# MCU.net
KiCad netlist of a schematic drawn in Altium Designer
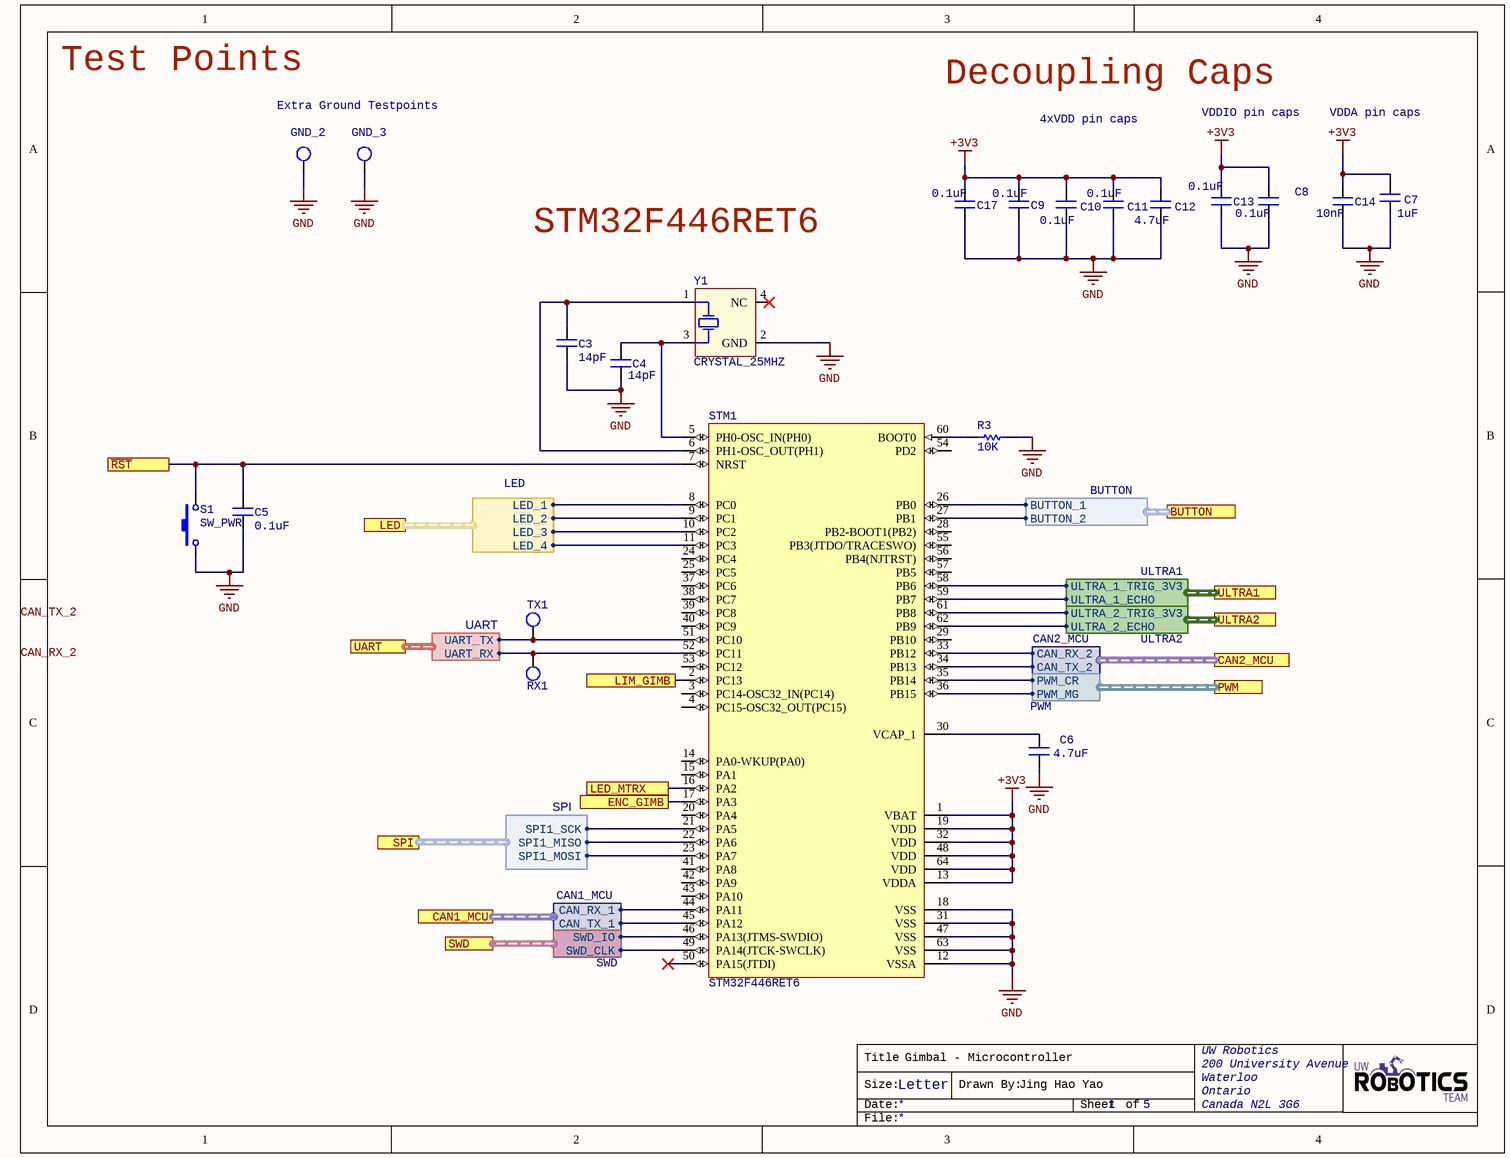
[diagram p0: MCU.SchDoc]

(export (version "E")
  (design (tool "Eeschema 10.0.6"))
  (components
    (comp (ref "C3")
      (value "14pF")
      (footprint "CAPC0603(1608)55_N")
      (description "Cap Ceramic 14pF 50V C0G 5% SMD 0603 125C Cardboard T/R")
      (fields (field (name "TOLERANCE") "5%") (field (name "Comment") "CL10C140JB8NNNC"))
      (libsource (lib "UWRT_Schematic_Library_2020") (part "CL10C140JB8NNNC"))
    )
    (comp (ref "C4")
      (value "14pF")
      (footprint "CAPC0603(1608)55_N")
      (description "Cap Ceramic 14pF 50V C0G 5% SMD 0603 125C Cardboard T/R")
      (fields (field (name "TOLERANCE") "5%") (field (name "Comment") "CL10C140JB8NNNC"))
      (libsource (lib "UWRT_Schematic_Library_2020") (part "CL10C140JB8NNNC"))
    )
    (comp (ref "C5")
      (value "0.1uF")
      (footprint "CAPC0603(1608)55_N")
      (description "CAP CER 0.1UF 16V X7R 0603")
      (fields (field (name "MANUFACTURER") "Yageo") (field (name "MPN") "CC0603KRX7R7BB104"))
      (libsource (lib "UWRT_Schematic_Library_2020") (part "CAP_0.1uF_16V_0603"))
    )
    (comp (ref "C6")
      (value "4.7uF")
      (footprint "CAPC0603(1608)55_N")
      (description "CAP CER 4.7UF 6.3V X5R 0603")
      (fields (field (name "MANUFACTURER") "Yageo") (field (name "MPN") "CC0603KRX5R5BB475"))
      (libsource (lib "UWRT_Schematic_Library_2020") (part "CAP_4.7uF_0603"))
    )
    (comp (ref "C7")
      (value "1uF")
      (footprint "CAPC0603(1608)55_N")
      (description "CAP CER 1UF 16V Y5V 0603")
      (fields (field (name "MANUFACTURER") "Yageo") (field (name "MPN") "CC0603ZRY5V7BB105"))
      (libsource (lib "UWRT_Schematic_Library_2020") (part "CAP_1uF_16V_0603"))
    )
    (comp (ref "C8")
      (value "0.1uF")
      (footprint "CAPC0603(1608)55_N")
      (description "CAP CER 0.1UF 16V X7R 0603")
      (fields (field (name "MANUFACTURER") "Yageo") (field (name "MPN") "CC0603KRX7R7BB104"))
      (libsource (lib "UWRT_Schematic_Library_2020") (part "CAP_0.1uF_16V_0603"))
    )
    (comp (ref "C9")
      (value "0.1uF")
      (footprint "CAPC0603(1608)55_N")
      (description "CAP CER 0.1UF 16V X7R 0603")
      (fields (field (name "MANUFACTURER") "Yageo") (field (name "MPN") "CC0603KRX7R7BB104"))
      (libsource (lib "UWRT_Schematic_Library_2020") (part "CAP_0.1uF_16V_0603"))
    )
    (comp (ref "C10")
      (value "0.1uF")
      (footprint "CAPC0603(1608)55_N")
      (description "CAP CER 0.1UF 16V X7R 0603")
      (fields (field (name "MANUFACTURER") "Yageo") (field (name "MPN") "CC0603KRX7R7BB104"))
      (libsource (lib "UWRT_Schematic_Library_2020") (part "CAP_0.1uF_16V_0603"))
    )
    (comp (ref "C11")
      (value "0.1uF")
      (footprint "CAPC0603(1608)55_N")
      (description "CAP CER 0.1UF 16V X7R 0603")
      (fields (field (name "MANUFACTURER") "Yageo") (field (name "MPN") "CC0603KRX7R7BB104"))
      (libsource (lib "UWRT_Schematic_Library_2020") (part "CAP_0.1uF_16V_0603"))
    )
    (comp (ref "C12")
      (value "4.7uF")
      (footprint "CAPC0603(1608)55_N")
      (description "CAP CER 4.7UF 6.3V X5R 0603")
      (fields (field (name "MANUFACTURER") "Yageo") (field (name "MPN") "CC0603KRX5R5BB475"))
      (libsource (lib "UWRT_Schematic_Library_2020") (part "CAP_4.7uF_0603"))
    )
    (comp (ref "C13")
      (value "0.1uF")
      (footprint "CAPC0603(1608)55_N")
      (description "CAP CER 0.1UF 16V X7R 0603")
      (fields (field (name "MANUFACTURER") "Yageo") (field (name "MPN") "CC0603KRX7R7BB104"))
      (libsource (lib "UWRT_Schematic_Library_2020") (part "CAP_0.1uF_16V_0603"))
    )
    (comp (ref "C14")
      (value "10nF")
      (footprint "CAPC0603(1608)55_N")
      (description "CAP CER 10000PF 16V X7R 0603")
      (fields (field (name "MANUFACTURER") "Yageo") (field (name "MPN") "CC0603KRX7R7BB103"))
      (libsource (lib "UWRT_Schematic_Library_2020") (part "CAP_10nF_0603"))
    )
    (comp (ref "C17")
      (value "0.1uF")
      (footprint "CAPC0603(1608)55_N")
      (description "CAP CER 0.1UF 16V X7R 0603")
      (fields (field (name "MANUFACTURER") "Yageo") (field (name "MPN") "CC0603KRX7R7BB104"))
      (libsource (lib "UWRT_Schematic_Library_2020") (part "CAP_0.1uF_16V_0603"))
    )
    (comp (ref "GND_2")
      (value "TESTPOINT_LOOP")
      (footprint "TESTPOINT_LOOP")
      (description "Loop testpoint through-hole pad")
      (fields (field (name "MANUFACTURER") "Keystone Electronics"))
      (libsource (lib "UWRT_Schematic_Library_2020") (part "TESTPOINT_LOOP"))
    )
    (comp (ref "GND_3")
      (value "TESTPOINT_LOOP")
      (footprint "TESTPOINT_LOOP")
      (description "Loop testpoint through-hole pad")
      (fields (field (name "MANUFACTURER") "Keystone Electronics"))
      (libsource (lib "UWRT_Schematic_Library_2020") (part "TESTPOINT_LOOP"))
    )
    (comp (ref "R3")
      (value "10K")
      (footprint "RESC0603(1608)_N")
      (description "RES SMD 10K OHM 5% 1/10W 0603")
      (fields (field (name "MANUFACTURER") "Yageo") (field (name "MPN") "RC0603JR-0710KL"))
      (libsource (lib "UWRT_Schematic_Library_2020") (part "RES_10K_0603"))
    )
    (comp (ref "RX1")
      (value "TESTPOINT_LOOP")
      (footprint "TESTPOINT_LOOP")
      (description "Loop testpoint through-hole pad")
      (fields (field (name "MANUFACTURER") "Keystone Electronics"))
      (libsource (lib "UWRT_Schematic_Library_2020") (part "TESTPOINT_LOOP"))
    )
    (comp (ref "S1")
      (value "SW_PWR")
      (footprint "PTS830GM140")
      (description "Power Switch (Red)")
      (fields (field (name "MPN") "PTS830GM140 SMTR LFS") (field (name "MANUFACTURER") "C&K"))
      (libsource (lib "UWRT_Schematic_Library_2020") (part "SW_PWR"))
    )
    (comp (ref "STM1")
      (value "STM32F446RET6")
      (footprint "STM-LQFP64_L")
      (libsource (lib "UWRT_Schematic_Library_2020") (part "MCU_STM32F446RET6"))
    )
    (comp (ref "TX1")
      (value "TESTPOINT_LOOP")
      (footprint "TESTPOINT_LOOP")
      (description "Loop testpoint through-hole pad")
      (fields (field (name "MANUFACTURER") "Keystone Electronics"))
      (libsource (lib "UWRT_Schematic_Library_2020") (part "TESTPOINT_LOOP"))
    )
    (comp (ref "Y1")
      (value "CRYSTAL_25MHZ")
      (footprint "AVX-CX2520DB32000D0GEJZ1-4_V")
      (description "CRYSTAL 25.0000MHZ 12PF SMD")
      (libsource (lib "UWRT_Schematic_Library_2020") (part "CRYSTAL_25MHZ"))
    )
  )
  (nets
    (net (code "11") (name "+3V3") (class "Default")
      (node (ref "C10") (pin "2") (pinfunction "2_2") (pintype "passive"))
      (node (ref "C11") (pin "2") (pinfunction "2_2") (pintype "passive"))
      (node (ref "C12") (pin "2") (pinfunction "2_2") (pintype "passive"))
      (node (ref "C13") (pin "2") (pinfunction "2_2") (pintype "passive"))
      (node (ref "C14") (pin "2") (pinfunction "2_2") (pintype "passive"))
      (node (ref "C17") (pin "2") (pinfunction "2_2") (pintype "passive"))
      (node (ref "C7") (pin "2") (pinfunction "2_2") (pintype "passive"))
      (node (ref "C8") (pin "2") (pinfunction "2_2") (pintype "passive"))
      (node (ref "C9") (pin "2") (pinfunction "2_2") (pintype "passive"))
      (node (ref "STM1") (pin "1") (pinfunction "VBAT_1") (pintype "power_in"))
      (node (ref "STM1") (pin "13") (pinfunction "VDDA_13") (pintype "power_in"))
      (node (ref "STM1") (pin "19") (pinfunction "VDD_19") (pintype "power_in"))
      (node (ref "STM1") (pin "32") (pinfunction "VDD_32") (pintype "power_in"))
      (node (ref "STM1") (pin "48") (pinfunction "VDD_48") (pintype "power_in"))
      (node (ref "STM1") (pin "64") (pinfunction "VDD_64") (pintype "power_in"))
    )
    (net (code "12") (name "/BUTTON_1") (class "Default")
      (node (ref "STM1") (pin "26") (pinfunction "PB0_26") (pintype "bidirectional"))
    )
    (net (code "13") (name "/BUTTON_2") (class "Default")
      (node (ref "STM1") (pin "27") (pinfunction "PB1_27") (pintype "bidirectional"))
    )
    (net (code "14") (name "/CAN_RX_1") (class "Default")
      (node (ref "STM1") (pin "44") (pinfunction "PA11_44") (pintype "bidirectional"))
    )
    (net (code "16") (name "/CAN_TX_1") (class "Default")
      (node (ref "STM1") (pin "45") (pinfunction "PA12_45") (pintype "bidirectional"))
    )
    (net (code "18") (name "/ENC_GIMB") (class "Default")
      (node (ref "STM1") (pin "17") (pinfunction "PA3_17") (pintype "bidirectional"))
    )
    (net (code "19") (name "/LED_1") (class "Default")
      (node (ref "STM1") (pin "8") (pinfunction "PC0_8") (pintype "bidirectional"))
    )
    (net (code "20") (name "/LED_2") (class "Default")
      (node (ref "STM1") (pin "9") (pinfunction "PC1_9") (pintype "bidirectional"))
    )
    (net (code "21") (name "/LED_3") (class "Default")
      (node (ref "STM1") (pin "10") (pinfunction "PC2_10") (pintype "bidirectional"))
    )
    (net (code "22") (name "/LED_4") (class "Default")
      (node (ref "STM1") (pin "11") (pinfunction "PC3_11") (pintype "bidirectional"))
    )
    (net (code "23") (name "/LED_MTRX") (class "Default")
      (node (ref "STM1") (pin "16") (pinfunction "PA2_16") (pintype "bidirectional"))
    )
    (net (code "24") (name "/LIM_GIMB") (class "Default")
      (node (ref "STM1") (pin "2") (pinfunction "PC13_2") (pintype "bidirectional"))
    )
    (net (code "25") (name "/PWM_CR") (class "Default")
      (node (ref "STM1") (pin "35") (pinfunction "PB14_35") (pintype "bidirectional"))
    )
    (net (code "26") (name "/PWM_MG") (class "Default")
      (node (ref "STM1") (pin "36") (pinfunction "PB15_36") (pintype "bidirectional"))
    )
    (net (code "27") (name "/SPI1_MISO") (class "Default")
      (node (ref "STM1") (pin "22") (pinfunction "PA6_22") (pintype "bidirectional"))
    )
    (net (code "28") (name "/SPI1_MOSI") (class "Default")
      (node (ref "STM1") (pin "23") (pinfunction "PA7_23") (pintype "bidirectional"))
    )
    (net (code "29") (name "/SPI1_SCK") (class "Default")
      (node (ref "STM1") (pin "21") (pinfunction "PA5_21") (pintype "bidirectional"))
    )
    (net (code "30") (name "/SWD_CLK") (class "Default")
      (node (ref "STM1") (pin "49") (pinfunction "PA14(JTCK-SWCLK)_49") (pintype "bidirectional"))
    )
    (net (code "31") (name "/SWD_IO") (class "Default")
      (node (ref "STM1") (pin "46") (pinfunction "PA13(JTMS-SWDIO)_46") (pintype "bidirectional"))
    )
    (net (code "32") (name "/UART_RX") (class "Default")
      (node (ref "RX1") (pin "1") (pintype "passive"))
      (node (ref "STM1") (pin "52") (pinfunction "PC11_52") (pintype "bidirectional"))
    )
    (net (code "33") (name "/UART_TX") (class "Default")
      (node (ref "STM1") (pin "51") (pinfunction "PC10_51") (pintype "bidirectional"))
      (node (ref "TX1") (pin "1") (pintype "passive"))
    )
    (net (code "34") (name "/ULTRA_1_ECHO") (class "Default")
      (node (ref "STM1") (pin "59") (pinfunction "PB7_59") (pintype "bidirectional"))
    )
    (net (code "35") (name "/ULTRA_1_TRIG_3V3") (class "Default")
      (node (ref "STM1") (pin "58") (pinfunction "PB6_58") (pintype "bidirectional"))
    )
    (net (code "36") (name "/ULTRA_2_ECHO") (class "Default")
      (node (ref "STM1") (pin "62") (pinfunction "PB9_62") (pintype "bidirectional"))
    )
    (net (code "37") (name "/ULTRA_2_TRIG_3V3") (class "Default")
      (node (ref "STM1") (pin "61") (pinfunction "PB8_61") (pintype "bidirectional"))
    )
    (net (code "48") (name "/~{RST}") (class "Default")
      (node (ref "C5") (pin "2") (pinfunction "2_2") (pintype "passive"))
      (node (ref "S1") (pin "2") (pinfunction "2_2") (pintype "passive"))
      (node (ref "STM1") (pin "7") (pinfunction "NRST_7") (pintype "bidirectional"))
    )
    (net (code "49") (name "GND") (class "Default")
      (node (ref "C10") (pin "1") (pinfunction "1_1") (pintype "passive"))
      (node (ref "C11") (pin "1") (pinfunction "1_1") (pintype "passive"))
      (node (ref "C12") (pin "1") (pinfunction "1_1") (pintype "passive"))
      (node (ref "C13") (pin "1") (pinfunction "1_1") (pintype "passive"))
      (node (ref "C14") (pin "1") (pinfunction "1_1") (pintype "passive"))
      (node (ref "C17") (pin "1") (pinfunction "1_1") (pintype "passive"))
      (node (ref "C3") (pin "1") (pinfunction "1_1") (pintype "passive"))
      (node (ref "C4") (pin "1") (pinfunction "1_1") (pintype "passive"))
      (node (ref "C5") (pin "1") (pinfunction "1_1") (pintype "passive"))
      (node (ref "C6") (pin "1") (pinfunction "1_1") (pintype "passive"))
      (node (ref "C7") (pin "1") (pinfunction "1_1") (pintype "passive"))
      (node (ref "C8") (pin "1") (pinfunction "1_1") (pintype "passive"))
      (node (ref "C9") (pin "1") (pinfunction "1_1") (pintype "passive"))
      (node (ref "GND_2") (pin "1") (pintype "passive"))
      (node (ref "GND_3") (pin "1") (pintype "passive"))
      (node (ref "R3") (pin "2") (pinfunction "2_2") (pintype "passive"))
      (node (ref "S1") (pin "1") (pinfunction "1_1") (pintype "passive"))
      (node (ref "STM1") (pin "12") (pinfunction "VSSA_12") (pintype "power_in"))
      (node (ref "STM1") (pin "18") (pinfunction "VSS_18") (pintype "power_in"))
      (node (ref "STM1") (pin "31") (pinfunction "VSS_31") (pintype "power_in"))
      (node (ref "STM1") (pin "47") (pinfunction "VSS_47") (pintype "power_in"))
      (node (ref "STM1") (pin "63") (pinfunction "VSS_63") (pintype "power_in"))
      (node (ref "Y1") (pin "2") (pinfunction "GND_2") (pintype "power_in"))
    )
    (net (code "50") (name "Net-(STM1-BOOT0)") (class "Default")
      (node (ref "R3") (pin "1") (pinfunction "1_1") (pintype "passive"))
      (node (ref "STM1") (pin "60") (pinfunction "BOOT0_60") (pintype "input"))
    )
    (net (code "51") (name "Net-(STM1-PH0-OSC_IN(PH0))") (class "Default")
      (node (ref "C4") (pin "2") (pinfunction "2_2") (pintype "passive"))
      (node (ref "STM1") (pin "5") (pinfunction "PH0-OSC_IN(PH0)_5") (pintype "bidirectional"))
      (node (ref "Y1") (pin "3") (pinfunction "HOT_3") (pintype "passive"))
    )
    (net (code "52") (name "Net-(STM1-PH1-OSC_OUT(PH1))") (class "Default")
      (node (ref "C3") (pin "2") (pinfunction "2_2") (pintype "passive"))
      (node (ref "STM1") (pin "6") (pinfunction "PH1-OSC_OUT(PH1)_6") (pintype "bidirectional"))
      (node (ref "Y1") (pin "1") (pinfunction "HOT_1") (pintype "passive"))
    )
    (net (code "53") (name "Net-(STM1-VCAP_1)") (class "Default")
      (node (ref "C6") (pin "2") (pinfunction "2_2") (pintype "passive"))
      (node (ref "STM1") (pin "30") (pinfunction "VCAP_1_30") (pintype "passive"))
    )
    (net (code "54") (name "unconnected-(STM1-PA0-WKUP(PA0)-Pad14)") (class "Default")
      (node (ref "STM1") (pin "14") (pinfunction "PA0-WKUP(PA0)_14") (pintype "bidirectional"))
    )
    (net (code "55") (name "unconnected-(STM1-PA1-Pad15)") (class "Default")
      (node (ref "STM1") (pin "15") (pinfunction "PA1_15") (pintype "bidirectional"))
    )
    (net (code "56") (name "unconnected-(STM1-PA4-Pad20)") (class "Default")
      (node (ref "STM1") (pin "20") (pinfunction "PA4_20") (pintype "bidirectional"))
    )
    (net (code "57") (name "unconnected-(STM1-PA8-Pad41)") (class "Default")
      (node (ref "STM1") (pin "41") (pinfunction "PA8_41") (pintype "bidirectional"))
    )
    (net (code "58") (name "unconnected-(STM1-PA9-Pad42)") (class "Default")
      (node (ref "STM1") (pin "42") (pinfunction "PA9_42") (pintype "bidirectional"))
    )
    (net (code "59") (name "unconnected-(STM1-PA10-Pad43)") (class "Default")
      (node (ref "STM1") (pin "43") (pinfunction "PA10_43") (pintype "bidirectional"))
    )
    (net (code "60") (name "unconnected-(STM1-PA15(JTDI)-Pad50)") (class "Default")
      (node (ref "STM1") (pin "50") (pinfunction "PA15(JTDI)_50") (pintype "bidirectional+no_connect"))
    )
    (net (code "61") (name "unconnected-(STM1-PB2-BOOT1(PB2)-Pad28)") (class "Default")
      (node (ref "STM1") (pin "28") (pinfunction "PB2-BOOT1(PB2)_28") (pintype "bidirectional"))
    )
    (net (code "62") (name "unconnected-(STM1-PB3(JTDO{slash}TRACESWO)-Pad55)") (class "Default")
      (node (ref "STM1") (pin "55") (pinfunction "PB3(JTDO/TRACESWO)_55") (pintype "bidirectional"))
    )
    (net (code "63") (name "unconnected-(STM1-PB4(NJTRST)-Pad56)") (class "Default")
      (node (ref "STM1") (pin "56") (pinfunction "PB4(NJTRST)_56") (pintype "bidirectional"))
    )
    (net (code "64") (name "unconnected-(STM1-PB5-Pad57)") (class "Default")
      (node (ref "STM1") (pin "57") (pinfunction "PB5_57") (pintype "bidirectional"))
    )
    (net (code "65") (name "unconnected-(STM1-PB10-Pad29)") (class "Default")
      (node (ref "STM1") (pin "29") (pinfunction "PB10_29") (pintype "bidirectional"))
    )
    (net (code "66") (name "unconnected-(STM1-PB12-Pad33)") (class "Default")
      (node (ref "STM1") (pin "33") (pinfunction "PB12_33") (pintype "bidirectional"))
    )
    (net (code "67") (name "unconnected-(STM1-PB13-Pad34)") (class "Default")
      (node (ref "STM1") (pin "34") (pinfunction "PB13_34") (pintype "bidirectional"))
    )
    (net (code "68") (name "unconnected-(STM1-PC4-Pad24)") (class "Default")
      (node (ref "STM1") (pin "24") (pinfunction "PC4_24") (pintype "bidirectional"))
    )
    (net (code "69") (name "unconnected-(STM1-PC5-Pad25)") (class "Default")
      (node (ref "STM1") (pin "25") (pinfunction "PC5_25") (pintype "bidirectional"))
    )
    (net (code "70") (name "unconnected-(STM1-PC6-Pad37)") (class "Default")
      (node (ref "STM1") (pin "37") (pinfunction "PC6_37") (pintype "bidirectional"))
    )
    (net (code "71") (name "unconnected-(STM1-PC7-Pad38)") (class "Default")
      (node (ref "STM1") (pin "38") (pinfunction "PC7_38") (pintype "bidirectional"))
    )
    (net (code "72") (name "unconnected-(STM1-PC8-Pad39)") (class "Default")
      (node (ref "STM1") (pin "39") (pinfunction "PC8_39") (pintype "bidirectional"))
    )
    (net (code "73") (name "unconnected-(STM1-PC9-Pad40)") (class "Default")
      (node (ref "STM1") (pin "40") (pinfunction "PC9_40") (pintype "bidirectional"))
    )
    (net (code "74") (name "unconnected-(STM1-PC12-Pad53)") (class "Default")
      (node (ref "STM1") (pin "53") (pinfunction "PC12_53") (pintype "bidirectional"))
    )
    (net (code "75") (name "unconnected-(STM1-PC14-OSC32_IN(PC14)-Pad3)") (class "Default")
      (node (ref "STM1") (pin "3") (pinfunction "PC14-OSC32_IN(PC14)_3") (pintype "bidirectional"))
    )
    (net (code "76") (name "unconnected-(STM1-PC15-OSC32_OUT(PC15)-Pad4)") (class "Default")
      (node (ref "STM1") (pin "4") (pinfunction "PC15-OSC32_OUT(PC15)_4") (pintype "bidirectional"))
    )
    (net (code "77") (name "unconnected-(STM1-PD2-Pad54)") (class "Default")
      (node (ref "STM1") (pin "54") (pinfunction "PD2_54") (pintype "bidirectional"))
    )
    (net (code "78") (name "unconnected-(Y1-NC-Pad4)") (class "Default")
      (node (ref "Y1") (pin "4") (pinfunction "NC_4") (pintype "passive+no_connect"))
    )
  )
)
